# UTX_EE445M_Front_LiDAR_Board_1.net
KiCad netlist of a schematic drawn in EAGLE
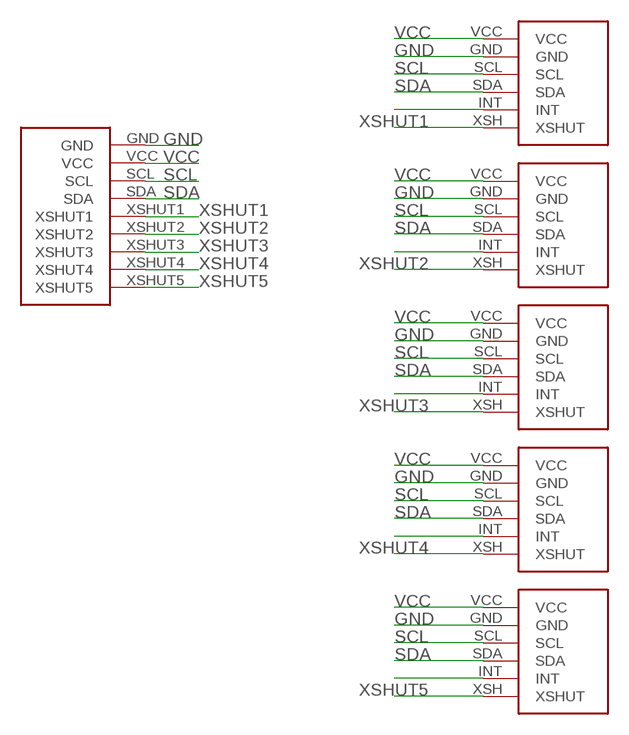
[diagram p0: schematic, sheet 1]

(export (version "E")
  (design (tool "Eeschema 10.0.6"))
  (components
    (comp (ref "U$1")
      (value "UTX_EE445M_LIDAR_FRONT_BOARD_CONNECTOR_PTH")
      (footprint "eagle-import:UTX_EE445M_LIDAR_FRONT_BOARD_CONNECTOR_PTH")
      (libsource (lib "eagle-import") (part "UTX_EE445M_LIDAR_FRONT_BOARD_CONNECTOR_PTH"))
    )
    (comp (ref "U$2")
      (value "LIDAR_VL53L0X_ATK_VERT")
      (footprint "eagle-import:LIDAR_VL53L0X_ATK_VERT")
      (libsource (lib "eagle-import") (part "LIDAR_VL53L0X_ATK_VERT"))
    )
    (comp (ref "U$3")
      (value "LIDAR_VL53L0X_ATK_VERT")
      (footprint "eagle-import:LIDAR_VL53L0X_ATK_VERT")
      (libsource (lib "eagle-import") (part "LIDAR_VL53L0X_ATK_VERT"))
    )
    (comp (ref "U$4")
      (value "LIDAR_VL53L0X_ATK_VERT")
      (footprint "eagle-import:LIDAR_VL53L0X_ATK_VERT")
      (libsource (lib "eagle-import") (part "LIDAR_VL53L0X_ATK_VERT"))
    )
    (comp (ref "U$5")
      (value "LIDAR_VL53L0X_ATK_VERT")
      (footprint "eagle-import:LIDAR_VL53L0X_ATK_VERT")
      (libsource (lib "eagle-import") (part "LIDAR_VL53L0X_ATK_VERT"))
    )
    (comp (ref "U$6")
      (value "LIDAR_VL53L0X_ATK_VERT")
      (footprint "eagle-import:LIDAR_VL53L0X_ATK_VERT")
      (libsource (lib "eagle-import") (part "LIDAR_VL53L0X_ATK_VERT"))
    )
  )
  (nets
    (net (code "1") (name "/GND") (class "Default")
      (node (ref "U$1") (pin "GND") (pinfunction "GND_GND") (pintype "bidirectional"))
      (node (ref "U$2") (pin "GND") (pinfunction "GND_GND") (pintype "bidirectional"))
      (node (ref "U$3") (pin "GND") (pinfunction "GND_GND") (pintype "bidirectional"))
      (node (ref "U$4") (pin "GND") (pinfunction "GND_GND") (pintype "bidirectional"))
      (node (ref "U$5") (pin "GND") (pinfunction "GND_GND") (pintype "bidirectional"))
      (node (ref "U$6") (pin "GND") (pinfunction "GND_GND") (pintype "bidirectional"))
    )
    (net (code "2") (name "/SCL") (class "Default")
      (node (ref "U$1") (pin "SCL") (pinfunction "SCL_SCL") (pintype "bidirectional"))
      (node (ref "U$2") (pin "SCL") (pinfunction "SCL_SCL") (pintype "bidirectional"))
      (node (ref "U$3") (pin "SCL") (pinfunction "SCL_SCL") (pintype "bidirectional"))
      (node (ref "U$4") (pin "SCL") (pinfunction "SCL_SCL") (pintype "bidirectional"))
      (node (ref "U$5") (pin "SCL") (pinfunction "SCL_SCL") (pintype "bidirectional"))
      (node (ref "U$6") (pin "SCL") (pinfunction "SCL_SCL") (pintype "bidirectional"))
    )
    (net (code "3") (name "/SDA") (class "Default")
      (node (ref "U$1") (pin "SDA") (pinfunction "SDA_SDA") (pintype "bidirectional"))
      (node (ref "U$2") (pin "SDA") (pinfunction "SDA_SDA") (pintype "bidirectional"))
      (node (ref "U$3") (pin "SDA") (pinfunction "SDA_SDA") (pintype "bidirectional"))
      (node (ref "U$4") (pin "SDA") (pinfunction "SDA_SDA") (pintype "bidirectional"))
      (node (ref "U$5") (pin "SDA") (pinfunction "SDA_SDA") (pintype "bidirectional"))
      (node (ref "U$6") (pin "SDA") (pinfunction "SDA_SDA") (pintype "bidirectional"))
    )
    (net (code "4") (name "/VCC") (class "Default")
      (node (ref "U$1") (pin "VCC") (pinfunction "VCC_VCC") (pintype "bidirectional"))
      (node (ref "U$2") (pin "VCC") (pinfunction "VCC_VCC") (pintype "bidirectional"))
      (node (ref "U$3") (pin "VCC") (pinfunction "VCC_VCC") (pintype "bidirectional"))
      (node (ref "U$4") (pin "VCC") (pinfunction "VCC_VCC") (pintype "bidirectional"))
      (node (ref "U$5") (pin "VCC") (pinfunction "VCC_VCC") (pintype "bidirectional"))
      (node (ref "U$6") (pin "VCC") (pinfunction "VCC_VCC") (pintype "bidirectional"))
    )
    (net (code "5") (name "/XSHUT1") (class "Default")
      (node (ref "U$1") (pin "XSHUT1") (pinfunction "XSHUT1_XSHUT1") (pintype "bidirectional"))
      (node (ref "U$2") (pin "XSH") (pinfunction "XSHUT_XSH") (pintype "bidirectional"))
    )
    (net (code "6") (name "/XSHUT2") (class "Default")
      (node (ref "U$1") (pin "XSHUT2") (pinfunction "XSHUT2_XSHUT2") (pintype "bidirectional"))
      (node (ref "U$3") (pin "XSH") (pinfunction "XSHUT_XSH") (pintype "bidirectional"))
    )
    (net (code "7") (name "/XSHUT3") (class "Default")
      (node (ref "U$1") (pin "XSHUT3") (pinfunction "XSHUT3_XSHUT3") (pintype "bidirectional"))
      (node (ref "U$4") (pin "XSH") (pinfunction "XSHUT_XSH") (pintype "bidirectional"))
    )
    (net (code "8") (name "/XSHUT4") (class "Default")
      (node (ref "U$1") (pin "XSHUT4") (pinfunction "XSHUT4_XSHUT4") (pintype "bidirectional"))
      (node (ref "U$5") (pin "XSH") (pinfunction "XSHUT_XSH") (pintype "bidirectional"))
    )
    (net (code "9") (name "/XSHUT5") (class "Default")
      (node (ref "U$1") (pin "XSHUT5") (pinfunction "XSHUT5_XSHUT5") (pintype "bidirectional"))
      (node (ref "U$6") (pin "XSH") (pinfunction "XSHUT_XSH") (pintype "bidirectional"))
    )
    (net (code "10") (name "unconnected-(U$2-PadINT)") (class "Default")
      (node (ref "U$2") (pin "INT") (pinfunction "INT_INT") (pintype "bidirectional"))
    )
    (net (code "11") (name "unconnected-(U$3-PadINT)") (class "Default")
      (node (ref "U$3") (pin "INT") (pinfunction "INT_INT") (pintype "bidirectional"))
    )
    (net (code "12") (name "unconnected-(U$4-PadINT)") (class "Default")
      (node (ref "U$4") (pin "INT") (pinfunction "INT_INT") (pintype "bidirectional"))
    )
    (net (code "13") (name "unconnected-(U$5-PadINT)") (class "Default")
      (node (ref "U$5") (pin "INT") (pinfunction "INT_INT") (pintype "bidirectional"))
    )
    (net (code "14") (name "unconnected-(U$6-PadINT)") (class "Default")
      (node (ref "U$6") (pin "INT") (pinfunction "INT_INT") (pintype "bidirectional"))
    )
  )
)
